# MAGIsCoCore.net
KiCad netlist of a schematic drawn in Altium Designer
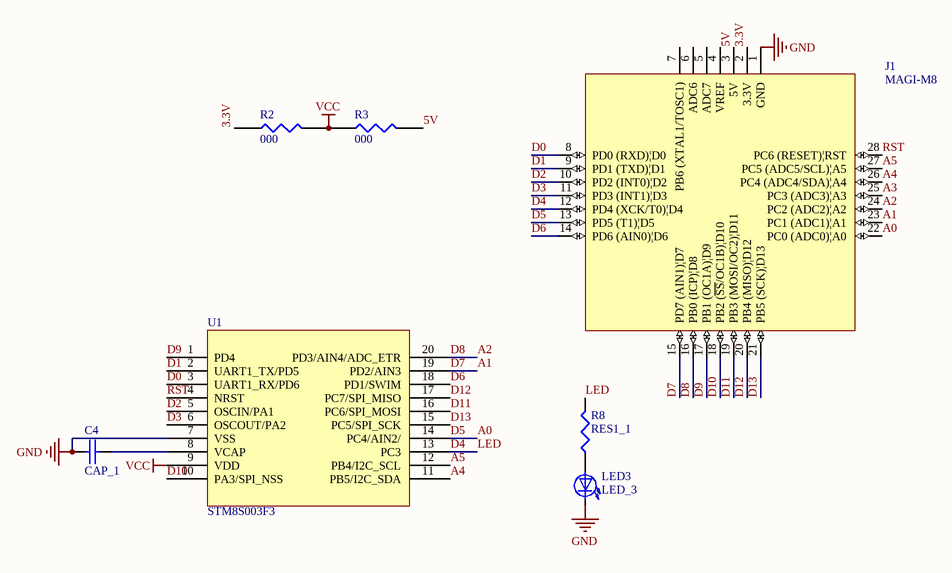
[diagram p0: MAGIsCoCore.SchDoc]

(export (version "E")
  (design (tool "Eeschema 10.0.6"))
  (components
    (comp (ref "C4")
      (value "CAP_1")
      (footprint "6-0805_N")
      (description "Capacitor")
      (libsource (lib "电容器") (part "CAP_1"))
    )
    (comp (ref "J1") (value "MAGI-M8") (footprint "MAGI-M8") (libsource (lib "MAGI-M8") (part "MAGI-M8")))
    (comp (ref "LED3") (value "LED_3") (footprint "6-0805_N") (libsource (lib "二极管") (part "LED_3")))
    (comp (ref "R2") (value "000") (footprint "6-0805_n") (libsource (lib "电阻器") (part "RES1")))
    (comp (ref "R3") (value "000") (footprint "6-0805_n") (libsource (lib "电阻器") (part "RES1")))
    (comp (ref "R8") (value "RES1_1") (footprint "6-0805_N") (libsource (lib "电阻器") (part "RES1_1")))
    (comp (ref "U1")
      (value "STM8S003F3")
      (footprint "STM8S003F3")
      (libsource (lib "MCU") (part "STM8S003F3"))
    )
  )
  (nets
    (net (code "1") (name "/3.3V") (class "Default")
      (node (ref "J1") (pin "2") (pinfunction "3.3V_2") (pintype "power_in"))
      (node (ref "R2") (pin "1") (pinfunction "1_1") (pintype "passive"))
    )
    (net (code "2") (name "/5V") (class "Default")
      (node (ref "J1") (pin "3") (pinfunction "5V_3") (pintype "power_in"))
      (node (ref "R3") (pin "2") (pinfunction "2_2") (pintype "passive"))
    )
    (net (code "3") (name "/A0") (class "Default")
      (node (ref "J1") (pin "13") (pinfunction "PD5_(T1)¦D5_13") (pintype "bidirectional"))
      (node (ref "J1") (pin "22") (pinfunction "PC0_(ADC0)¦A0_22") (pintype "bidirectional"))
      (node (ref "U1") (pin "14") (pinfunction "PC4/AIN2/_14") (pintype "passive"))
    )
    (net (code "4") (name "/A1") (class "Default")
      (node (ref "J1") (pin "15") (pinfunction "PD7_(AIN1)¦D7_15") (pintype "bidirectional"))
      (node (ref "J1") (pin "23") (pinfunction "PC1_(ADC1)¦A1_23") (pintype "bidirectional"))
      (node (ref "U1") (pin "19") (pinfunction "PD2/AIN3_19") (pintype "passive"))
    )
    (net (code "5") (name "/A2") (class "Default")
      (node (ref "J1") (pin "16") (pinfunction "PB0_(ICP)¦D8_16") (pintype "bidirectional"))
      (node (ref "J1") (pin "24") (pinfunction "PC2_(ADC2)¦A2_24") (pintype "bidirectional"))
      (node (ref "U1") (pin "20") (pinfunction "PD3/AIN4/ADC_ETR_20") (pintype "passive"))
    )
    (net (code "6") (name "/A3") (class "Default")
      (node (ref "J1") (pin "25") (pinfunction "PC3_(ADC3)¦A3_25") (pintype "bidirectional"))
    )
    (net (code "7") (name "/A4") (class "Default")
      (node (ref "J1") (pin "26") (pinfunction "PC4_(ADC4/SDA)¦A4_26") (pintype "bidirectional"))
      (node (ref "U1") (pin "11") (pinfunction "PB5/I2C_SDA_11") (pintype "passive"))
    )
    (net (code "8") (name "/A5") (class "Default")
      (node (ref "J1") (pin "27") (pinfunction "PC5_(ADC5/SCL)¦A5_27") (pintype "bidirectional"))
      (node (ref "U1") (pin "12") (pinfunction "PB4/I2C_SCL_12") (pintype "passive"))
    )
    (net (code "9") (name "/D0") (class "Default")
      (node (ref "J1") (pin "8") (pinfunction "PD0_(RXD)¦D0_8") (pintype "bidirectional"))
      (node (ref "U1") (pin "3") (pinfunction "UART1_RX/PD6_3") (pintype "passive"))
    )
    (net (code "10") (name "/D1") (class "Default")
      (node (ref "J1") (pin "9") (pinfunction "PD1_(TXD)¦D1_9") (pintype "bidirectional"))
      (node (ref "U1") (pin "2") (pinfunction "UART1_TX/PD5_2") (pintype "passive"))
    )
    (net (code "11") (name "/D2") (class "Default")
      (node (ref "J1") (pin "10") (pinfunction "PD2_(INT0)¦D2_10") (pintype "bidirectional"))
      (node (ref "U1") (pin "5") (pinfunction "OSCIN/PA1_5") (pintype "passive"))
    )
    (net (code "12") (name "/D3") (class "Default")
      (node (ref "J1") (pin "11") (pinfunction "PD3_(INT1)¦D3_11") (pintype "bidirectional"))
      (node (ref "U1") (pin "6") (pinfunction "OSCOUT/PA2_6") (pintype "passive"))
    )
    (net (code "13") (name "/D4") (class "Default")
      (node (ref "J1") (pin "12") (pinfunction "PD4_(XCK/T0)¦D4_12") (pintype "bidirectional"))
      (node (ref "R8") (pin "2") (pinfunction "2_2") (pintype "passive"))
      (node (ref "U1") (pin "13") (pinfunction "PC3_13") (pintype "passive"))
    )
    (net (code "14") (name "/D6") (class "Default")
      (node (ref "J1") (pin "14") (pinfunction "PD6_(AIN0)¦D6_14") (pintype "bidirectional"))
      (node (ref "U1") (pin "18") (pinfunction "PD1/SWIM_18") (pintype "passive"))
    )
    (net (code "15") (name "/D9") (class "Default")
      (node (ref "J1") (pin "17") (pinfunction "PB1_(OC1A)¦D9_17") (pintype "bidirectional"))
      (node (ref "U1") (pin "1") (pinfunction "PD4_1") (pintype "passive"))
    )
    (net (code "16") (name "/D10") (class "Default")
      (node (ref "J1") (pin "18") (pinfunction "PB2_(~{SS}/OC1B)¦D10_18") (pintype "bidirectional"))
      (node (ref "U1") (pin "10") (pinfunction "PA3/SPI_NSS_10") (pintype "passive"))
    )
    (net (code "17") (name "/D11") (class "Default")
      (node (ref "J1") (pin "19") (pinfunction "PB3_(MOSI/OC2)¦D11_19") (pintype "bidirectional"))
      (node (ref "U1") (pin "16") (pinfunction "PC6/SPI_MOSI_16") (pintype "passive"))
    )
    (net (code "18") (name "/D12") (class "Default")
      (node (ref "J1") (pin "20") (pinfunction "PB4_(MISO)¦D12_20") (pintype "bidirectional"))
      (node (ref "U1") (pin "17") (pinfunction "PC7/SPI_MISO_17") (pintype "passive"))
    )
    (net (code "19") (name "/D13") (class "Default")
      (node (ref "J1") (pin "21") (pinfunction "PB5_(SCK)¦D13_21") (pintype "bidirectional"))
      (node (ref "U1") (pin "15") (pinfunction "PC5/SPI_SCK_15") (pintype "passive"))
    )
    (net (code "20") (name "/RST") (class "Default")
      (node (ref "J1") (pin "28") (pinfunction "PC6_(RESET)¦RST_28") (pintype "bidirectional"))
      (node (ref "U1") (pin "4") (pinfunction "NRST_4") (pintype "passive"))
    )
    (net (code "21") (name "GND") (class "Default")
      (node (ref "C4") (pin "1") (pinfunction "1_1") (pintype "passive"))
      (node (ref "J1") (pin "1") (pinfunction "GND_1") (pintype "power_in"))
      (node (ref "LED3") (pin "2") (pinfunction "K_2") (pintype "passive"))
      (node (ref "U1") (pin "7") (pinfunction "VSS_7") (pintype "passive"))
    )
    (net (code "22") (name "Net-(LED3-A)") (class "Default")
      (node (ref "LED3") (pin "1") (pinfunction "A_1") (pintype "passive"))
      (node (ref "R8") (pin "1") (pinfunction "1_1") (pintype "passive"))
    )
    (net (code "23") (name "Net-(U1-VCAP)") (class "Default")
      (node (ref "C4") (pin "2") (pinfunction "2_2") (pintype "passive"))
      (node (ref "U1") (pin "8") (pinfunction "VCAP_8") (pintype "passive"))
    )
    (net (code "24") (name "VCC") (class "Default")
      (node (ref "R2") (pin "2") (pinfunction "2_2") (pintype "passive"))
      (node (ref "R3") (pin "1") (pinfunction "1_1") (pintype "passive"))
      (node (ref "U1") (pin "9") (pinfunction "VDD_9") (pintype "passive"))
    )
    (net (code "25") (name "unconnected-(J1-ADC6-Pad6)") (class "Default")
      (node (ref "J1") (pin "6") (pinfunction "ADC6_6") (pintype "passive"))
    )
    (net (code "26") (name "unconnected-(J1-ADC7-Pad5)") (class "Default")
      (node (ref "J1") (pin "5") (pinfunction "ADC7_5") (pintype "passive"))
    )
    (net (code "27") (name "unconnected-(J1-PB6_(XTAL1{slash}TOSC1)-Pad7)") (class "Default")
      (node (ref "J1") (pin "7") (pinfunction "PB6_(XTAL1/TOSC1)_7") (pintype "passive"))
    )
    (net (code "28") (name "unconnected-(J1-VREF-Pad4)") (class "Default")
      (node (ref "J1") (pin "4") (pinfunction "VREF_4") (pintype "passive"))
    )
  )
)
